# 51-2001-01-6_04_Power_Module_Schematic.net
KiCad netlist of a schematic drawn in Altium Designer
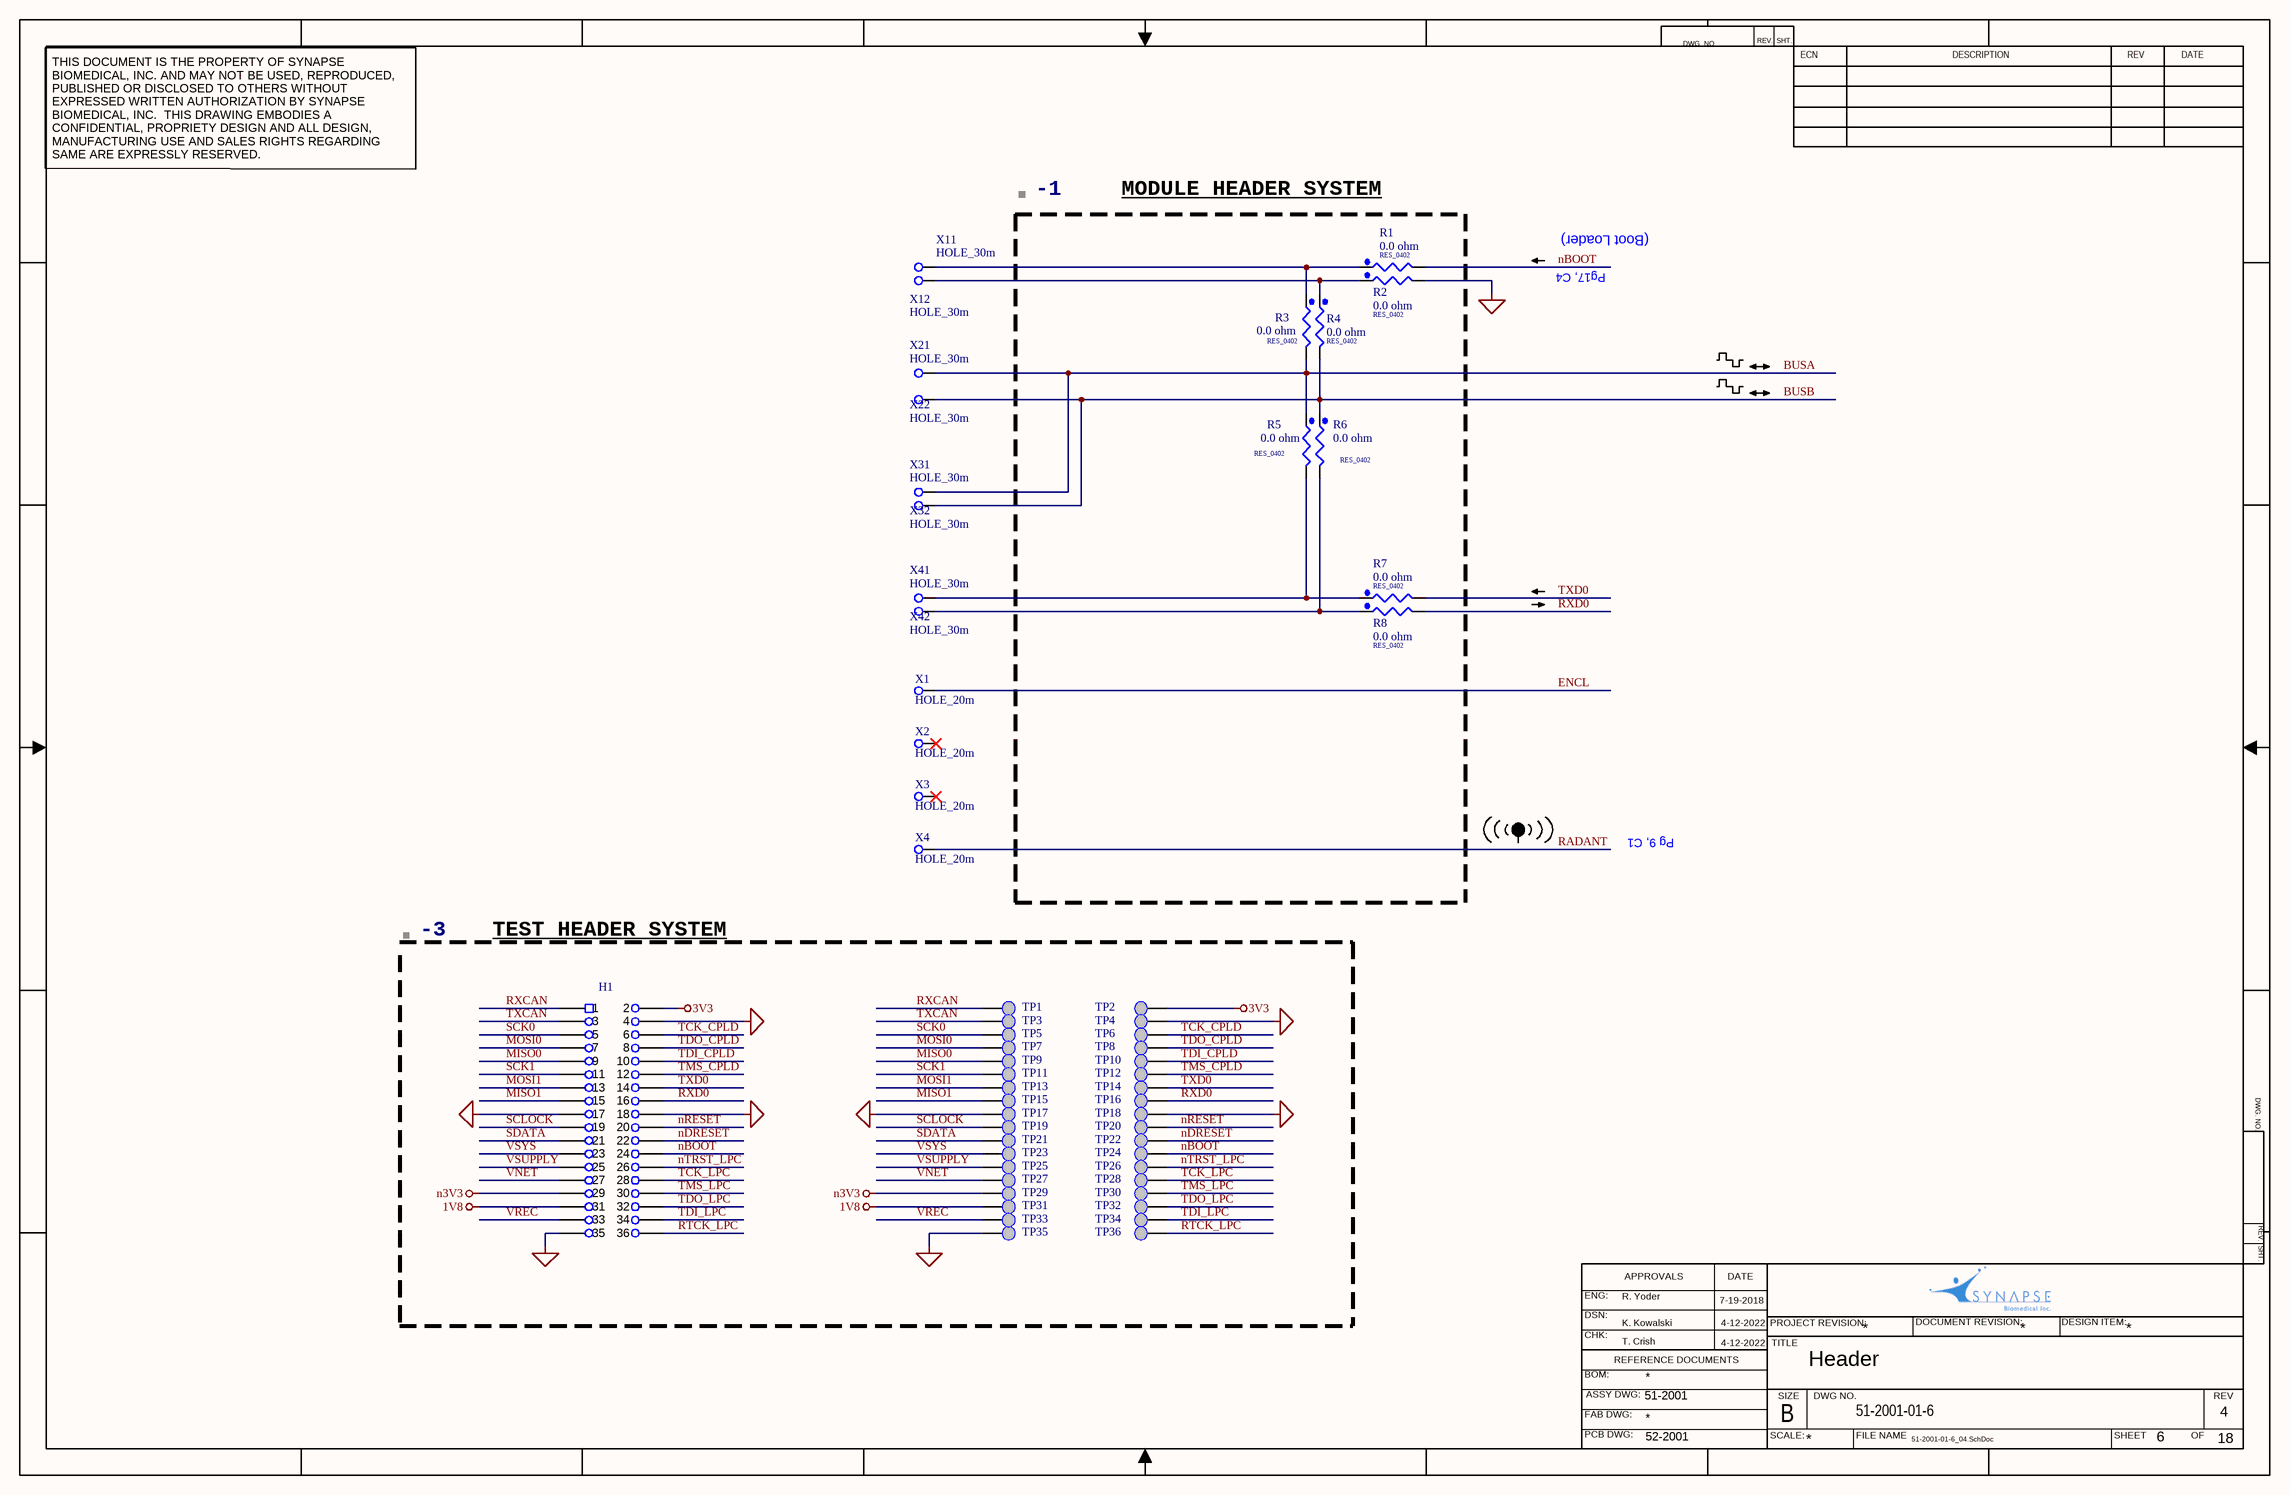
[diagram p0: 51-2001-01-6_04 Power Module Schematic.SchDoc]

(export (version "E")
  (design (tool "Eeschema 10.0.6"))
  (components
    (comp (ref "-1")
      (value "BOM_S1")
      (description "BOM item small graphic")
      (fields (field (name "XDESCRIPTION") "MODULE HEADER SYSTEM"))
      (libsource (lib "BOM_sym") (part "BOM_S1"))
    )
    (comp (ref "-3")
      (value "BOM_S1")
      (description "BOM item small graphic")
      (fields (field (name "XDESCRIPTION") "TEST HEADER SYSTEM"))
      (libsource (lib "BOM_sym") (part "BOM_S1"))
    )
    (comp (ref "H1")
      (value "0.1\"")
      (footprint "HEADER36")
      (description "0.1\" Header")
      (libsource (lib "NNPS Integrated Parts") (part "Header 2X18"))
    )
    (comp (ref "R1")
      (value "0.0 ohm")
      (footprint "RES_0402")
      (description "0.0 ohm, 1/16W, 0402, RoHS")
      (fields
        (field (name "MFR") "Vishay Dale")
        (field (name "PACKAGEDESCRIPTION") "RES_0402")
        (field (name "MPN") "CRCW04021K00FKED")
      )
      (libsource (lib "NNPS Integrated Parts") (part "MCR01MZPJ000"))
    )
    (comp (ref "R2")
      (value "0.0 ohm")
      (footprint "RES_0402")
      (description "0.0 ohm, 1/16W, 0402, RoHS")
      (fields
        (field (name "MFR") "Vishay Dale")
        (field (name "PACKAGEDESCRIPTION") "RES_0402")
        (field (name "MPN") "CRCW04021K00FKED")
      )
      (libsource (lib "NNPS Integrated Parts") (part "MCR01MZPJ000"))
    )
    (comp (ref "R3")
      (value "0.0 ohm")
      (footprint "RES_0402")
      (description "0.0 ohm, 1/16W, 0402, RoHS")
      (fields
        (field (name "MFR") "Vishay Dale")
        (field (name "PACKAGEDESCRIPTION") "RES_0402")
        (field (name "MPN") "CRCW04021K00FKED")
      )
      (libsource (lib "NNPS Integrated Parts") (part "MCR01MZPJ000"))
    )
    (comp (ref "R4")
      (value "0.0 ohm")
      (footprint "RES_0402")
      (description "0.0 ohm, 1/16W, 0402, RoHS")
      (fields
        (field (name "MFR") "Vishay Dale")
        (field (name "PACKAGEDESCRIPTION") "RES_0402")
        (field (name "MPN") "CRCW04021K00FKED")
      )
      (libsource (lib "NNPS Integrated Parts") (part "MCR01MZPJ000"))
    )
    (comp (ref "R5")
      (value "0.0 ohm")
      (footprint "RES_0402")
      (description "0.0 ohm, 1/16W, 0402, RoHS")
      (fields
        (field (name "MFR") "Vishay Dale")
        (field (name "PACKAGEDESCRIPTION") "RES_0402")
        (field (name "MPN") "CRCW04021K00FKED")
      )
      (libsource (lib "NNPS Integrated Parts") (part "MCR01MZPJ000"))
    )
    (comp (ref "R6")
      (value "0.0 ohm")
      (footprint "RES_0402")
      (description "0.0 ohm, 1/16W, 0402, RoHS")
      (fields
        (field (name "MFR") "Vishay Dale")
        (field (name "PACKAGEDESCRIPTION") "RES_0402")
        (field (name "MPN") "CRCW04021K00FKED")
      )
      (libsource (lib "NNPS Integrated Parts") (part "MCR01MZPJ000"))
    )
    (comp (ref "R7")
      (value "0.0 ohm")
      (footprint "RES_0402")
      (description "0.0 ohm, 1/16W, 0402, RoHS")
      (fields
        (field (name "MFR") "Vishay Dale")
        (field (name "PACKAGEDESCRIPTION") "RES_0402")
        (field (name "MPN") "CRCW04021K00FKED")
      )
      (libsource (lib "NNPS Integrated Parts") (part "MCR01MZPJ000"))
    )
    (comp (ref "R8")
      (value "0.0 ohm")
      (footprint "RES_0402")
      (description "0.0 ohm, 1/16W, 0402, RoHS")
      (fields
        (field (name "MFR") "Vishay Dale")
        (field (name "PACKAGEDESCRIPTION") "RES_0402")
        (field (name "MPN") "CRCW04021K00FKED")
      )
      (libsource (lib "NNPS Integrated Parts") (part "MCR01MZPJ000"))
    )
    (comp (ref "TP1")
      (value "Test Point")
      (footprint "TEST_POINT")
      (description "Test Point Pad 1.00 mm")
      (libsource (lib "PM1b") (part "TP"))
    )
    (comp (ref "TP2")
      (value "Test Point")
      (footprint "TEST_POINT")
      (description "Test Point Pad 1.00 mm")
      (libsource (lib "PM1b") (part "TP"))
    )
    (comp (ref "TP3")
      (value "Test Point")
      (footprint "TEST_POINT")
      (description "Test Point Pad 1.00 mm")
      (libsource (lib "PM1b") (part "TP"))
    )
    (comp (ref "TP4")
      (value "Test Point")
      (footprint "TEST_POINT")
      (description "Test Point Pad 1.00 mm")
      (libsource (lib "PM1b") (part "TP"))
    )
    (comp (ref "TP5")
      (value "Test Point")
      (footprint "TEST_POINT")
      (description "Test Point Pad 1.00 mm")
      (libsource (lib "PM1b") (part "TP"))
    )
    (comp (ref "TP6")
      (value "Test Point")
      (footprint "TEST_POINT")
      (description "Test Point Pad 1.00 mm")
      (libsource (lib "PM1b") (part "TP"))
    )
    (comp (ref "TP7")
      (value "Test Point")
      (footprint "TEST_POINT")
      (description "Test Point Pad 1.00 mm")
      (libsource (lib "PM1b") (part "TP"))
    )
    (comp (ref "TP8")
      (value "Test Point")
      (footprint "TEST_POINT")
      (description "Test Point Pad 1.00 mm")
      (libsource (lib "PM1b") (part "TP"))
    )
    (comp (ref "TP9")
      (value "Test Point")
      (footprint "TEST_POINT")
      (description "Test Point Pad 1.00 mm")
      (libsource (lib "PM1b") (part "TP"))
    )
    (comp (ref "TP10")
      (value "Test Point")
      (footprint "TEST_POINT")
      (description "Test Point Pad 1.00 mm")
      (libsource (lib "PM1b") (part "TP"))
    )
    (comp (ref "TP11")
      (value "Test Point")
      (footprint "TEST_POINT")
      (description "Test Point Pad 1.00 mm")
      (libsource (lib "PM1b") (part "TP"))
    )
    (comp (ref "TP12")
      (value "Test Point")
      (footprint "TEST_POINT")
      (description "Test Point Pad 1.00 mm")
      (libsource (lib "PM1b") (part "TP"))
    )
    (comp (ref "TP13")
      (value "Test Point")
      (footprint "TEST_POINT")
      (description "Test Point Pad 1.00 mm")
      (libsource (lib "PM1b") (part "TP"))
    )
    (comp (ref "TP14")
      (value "Test Point")
      (footprint "TEST_POINT")
      (description "Test Point Pad 1.00 mm")
      (libsource (lib "PM1b") (part "TP"))
    )
    (comp (ref "TP15")
      (value "Test Point")
      (footprint "TEST_POINT")
      (description "Test Point Pad 1.00 mm")
      (libsource (lib "PM1b") (part "TP"))
    )
    (comp (ref "TP16")
      (value "Test Point")
      (footprint "TEST_POINT")
      (description "Test Point Pad 1.00 mm")
      (libsource (lib "PM1b") (part "TP"))
    )
    (comp (ref "TP17")
      (value "Test Point")
      (footprint "TEST_POINT")
      (description "Test Point Pad 1.00 mm")
      (libsource (lib "PM1b") (part "TP"))
    )
    (comp (ref "TP18")
      (value "Test Point")
      (footprint "TEST_POINT")
      (description "Test Point Pad 1.00 mm")
      (libsource (lib "PM1b") (part "TP"))
    )
    (comp (ref "TP19")
      (value "Test Point")
      (footprint "TEST_POINT")
      (description "Test Point Pad 1.00 mm")
      (libsource (lib "PM1b") (part "TP"))
    )
    (comp (ref "TP20")
      (value "Test Point")
      (footprint "TEST_POINT")
      (description "Test Point Pad 1.00 mm")
      (libsource (lib "PM1b") (part "TP"))
    )
    (comp (ref "TP21")
      (value "Test Point")
      (footprint "TEST_POINT")
      (description "Test Point Pad 1.00 mm")
      (libsource (lib "PM1b") (part "TP"))
    )
    (comp (ref "TP22")
      (value "Test Point")
      (footprint "TEST_POINT")
      (description "Test Point Pad 1.00 mm")
      (libsource (lib "PM1b") (part "TP"))
    )
    (comp (ref "TP23")
      (value "Test Point")
      (footprint "TEST_POINT")
      (description "Test Point Pad 1.00 mm")
      (libsource (lib "PM1b") (part "TP"))
    )
    (comp (ref "TP24")
      (value "Test Point")
      (footprint "TEST_POINT")
      (description "Test Point Pad 1.00 mm")
      (libsource (lib "PM1b") (part "TP"))
    )
    (comp (ref "TP25")
      (value "Test Point")
      (footprint "TEST_POINT")
      (description "Test Point Pad 1.00 mm")
      (libsource (lib "PM1b") (part "TP"))
    )
    (comp (ref "TP26")
      (value "Test Point")
      (footprint "TEST_POINT")
      (description "Test Point Pad 1.00 mm")
      (libsource (lib "PM1b") (part "TP"))
    )
    (comp (ref "TP27")
      (value "Test Point")
      (footprint "TEST_POINT")
      (description "Test Point Pad 1.00 mm")
      (libsource (lib "PM1b") (part "TP"))
    )
    (comp (ref "TP28")
      (value "Test Point")
      (footprint "TEST_POINT")
      (description "Test Point Pad 1.00 mm")
      (libsource (lib "PM1b") (part "TP"))
    )
    (comp (ref "TP29")
      (value "Test Point")
      (footprint "TEST_POINT")
      (description "Test Point Pad 1.00 mm")
      (libsource (lib "PM1b") (part "TP"))
    )
    (comp (ref "TP30")
      (value "Test Point")
      (footprint "TEST_POINT")
      (description "Test Point Pad 1.00 mm")
      (libsource (lib "PM1b") (part "TP"))
    )
    (comp (ref "TP31")
      (value "Test Point")
      (footprint "TEST_POINT")
      (description "Test Point Pad 1.00 mm")
      (libsource (lib "PM1b") (part "TP"))
    )
    (comp (ref "TP32")
      (value "Test Point")
      (footprint "TEST_POINT")
      (description "Test Point Pad 1.00 mm")
      (libsource (lib "PM1b") (part "TP"))
    )
    (comp (ref "TP33")
      (value "Test Point")
      (footprint "TEST_POINT")
      (description "Test Point Pad 1.00 mm")
      (libsource (lib "PM1b") (part "TP"))
    )
    (comp (ref "TP34")
      (value "Test Point")
      (footprint "TEST_POINT")
      (description "Test Point Pad 1.00 mm")
      (libsource (lib "PM1b") (part "TP"))
    )
    (comp (ref "TP35")
      (value "Test Point")
      (footprint "TEST_POINT")
      (description "Test Point Pad 1.00 mm")
      (libsource (lib "PM1b") (part "TP"))
    )
    (comp (ref "TP36")
      (value "Test Point")
      (footprint "TEST_POINT")
      (description "Test Point Pad 1.00 mm")
      (libsource (lib "PM1b") (part "TP"))
    )
    (comp (ref "X1")
      (value "HOLE_20m")
      (footprint "FEEDHOLE_20mil")
      (description "Hole for 10mil diameter feedthrough")
      (libsource (lib "NNPS Integrated Parts") (part "HOLE_20m"))
    )
    (comp (ref "X2")
      (value "HOLE_20m")
      (footprint "FEEDHOLE_20mil")
      (description "Hole for 10mil diameter feedthrough")
      (libsource (lib "NNPS Integrated Parts") (part "HOLE_20m"))
    )
    (comp (ref "X3")
      (value "HOLE_20m")
      (footprint "FEEDHOLE_20mil")
      (description "Hole for 10mil diameter feedthrough")
      (libsource (lib "NNPS Integrated Parts") (part "HOLE_20m"))
    )
    (comp (ref "X4")
      (value "HOLE_20m")
      (footprint "FEEDHOLE_20mil")
      (description "Hole for 10mil diameter feedthrough")
      (libsource (lib "NNPS Integrated Parts") (part "HOLE_20m"))
    )
    (comp (ref "X11")
      (value "HOLE_30m")
      (footprint "FEEDHOLE_30mil")
      (description "Hole 30mil")
      (libsource (lib "NNPS Integrated Parts") (part "HOLE_30m"))
    )
    (comp (ref "X12")
      (value "HOLE_30m")
      (footprint "FEEDHOLE_30mil")
      (description "Hole 30mil")
      (libsource (lib "NNPS Integrated Parts") (part "HOLE_30m"))
    )
    (comp (ref "X21")
      (value "HOLE_30m")
      (footprint "FEEDHOLE_30mil")
      (description "Hole 30mil")
      (libsource (lib "NNPS Integrated Parts") (part "HOLE_30m"))
    )
    (comp (ref "X22")
      (value "HOLE_30m")
      (footprint "FEEDHOLE_30mil")
      (description "Hole 30mil")
      (libsource (lib "NNPS Integrated Parts") (part "HOLE_30m"))
    )
    (comp (ref "X31")
      (value "HOLE_30m")
      (footprint "FEEDHOLE_30mil")
      (description "Hole 30mil")
      (libsource (lib "NNPS Integrated Parts") (part "HOLE_30m"))
    )
    (comp (ref "X32")
      (value "HOLE_30m")
      (footprint "FEEDHOLE_30mil")
      (description "Hole 30mil")
      (libsource (lib "NNPS Integrated Parts") (part "HOLE_30m"))
    )
    (comp (ref "X41")
      (value "HOLE_30m")
      (footprint "FEEDHOLE_30mil")
      (description "Hole 30mil")
      (libsource (lib "NNPS Integrated Parts") (part "HOLE_30m"))
    )
    (comp (ref "X42")
      (value "HOLE_30m")
      (footprint "PCBComponent_11")
      (description "Hole 30mil")
      (libsource (lib "NNPS Integrated Parts") (part "HOLE_30m"))
    )
  )
  (nets
    (net (code "1") (name "/BUSA") (class "Default")
      (node (ref "R3") (pin "2") (pinfunction "2_2") (pintype "passive"))
      (node (ref "R5") (pin "1") (pinfunction "1_1") (pintype "passive"))
      (node (ref "X21") (pin "1") (pinfunction "1_1") (pintype "passive"))
      (node (ref "X31") (pin "1") (pinfunction "1_1") (pintype "passive"))
    )
    (net (code "2") (name "/BUSB") (class "Default")
      (node (ref "R4") (pin "2") (pinfunction "2_2") (pintype "passive"))
      (node (ref "R6") (pin "1") (pinfunction "1_1") (pintype "passive"))
      (node (ref "X22") (pin "1") (pinfunction "1_1") (pintype "passive"))
      (node (ref "X32") (pin "1") (pinfunction "1_1") (pintype "passive"))
    )
    (net (code "3") (name "/ENCL") (class "Default")
      (node (ref "X1") (pin "1") (pinfunction "1_1") (pintype "passive"))
    )
    (net (code "4") (name "/MISO0") (class "Default")
      (node (ref "H1") (pin "9") (pinfunction "9_9") (pintype "passive"))
      (node (ref "TP9") (pin "1") (pinfunction "TP_1") (pintype "passive"))
    )
    (net (code "5") (name "/MISO1") (class "Default")
      (node (ref "H1") (pin "15") (pinfunction "15_15") (pintype "passive"))
      (node (ref "TP15") (pin "1") (pinfunction "TP_1") (pintype "passive"))
    )
    (net (code "6") (name "/MOSI0") (class "Default")
      (node (ref "H1") (pin "7") (pinfunction "7_7") (pintype "passive"))
      (node (ref "TP7") (pin "1") (pinfunction "TP_1") (pintype "passive"))
    )
    (net (code "7") (name "/MOSI1") (class "Default")
      (node (ref "H1") (pin "13") (pinfunction "13_13") (pintype "passive"))
      (node (ref "TP13") (pin "1") (pinfunction "TP_1") (pintype "passive"))
    )
    (net (code "8") (name "/RADANT") (class "Default")
      (node (ref "X4") (pin "1") (pinfunction "1_1") (pintype "passive"))
    )
    (net (code "9") (name "/RTCK_LPC") (class "Default")
      (node (ref "H1") (pin "36") (pinfunction "36_36") (pintype "passive"))
      (node (ref "TP36") (pin "1") (pinfunction "TP_1") (pintype "passive"))
    )
    (net (code "10") (name "/RXCAN") (class "Default")
      (node (ref "H1") (pin "1") (pinfunction "1_1") (pintype "passive"))
      (node (ref "TP1") (pin "1") (pinfunction "TP_1") (pintype "passive"))
    )
    (net (code "11") (name "/RXD0") (class "Default")
      (node (ref "H1") (pin "16") (pinfunction "16_16") (pintype "passive"))
      (node (ref "R8") (pin "2") (pinfunction "2_2") (pintype "passive"))
      (node (ref "TP16") (pin "1") (pinfunction "TP_1") (pintype "passive"))
    )
    (net (code "12") (name "/SCK0") (class "Default")
      (node (ref "H1") (pin "5") (pinfunction "5_5") (pintype "passive"))
      (node (ref "TP5") (pin "1") (pinfunction "TP_1") (pintype "passive"))
    )
    (net (code "13") (name "/SCK1") (class "Default")
      (node (ref "H1") (pin "11") (pinfunction "11_11") (pintype "passive"))
      (node (ref "TP11") (pin "1") (pinfunction "TP_1") (pintype "passive"))
    )
    (net (code "14") (name "/SCLOCK") (class "Default")
      (node (ref "H1") (pin "19") (pinfunction "19_19") (pintype "passive"))
      (node (ref "TP19") (pin "1") (pinfunction "TP_1") (pintype "passive"))
    )
    (net (code "15") (name "/SDATA") (class "Default")
      (node (ref "H1") (pin "21") (pinfunction "21_21") (pintype "passive"))
      (node (ref "TP21") (pin "1") (pinfunction "TP_1") (pintype "passive"))
    )
    (net (code "16") (name "/TCK_CPLD") (class "Default")
      (node (ref "H1") (pin "6") (pinfunction "6_6") (pintype "passive"))
      (node (ref "TP6") (pin "1") (pinfunction "TP_1") (pintype "passive"))
    )
    (net (code "17") (name "/TCK_LPC") (class "Default")
      (node (ref "H1") (pin "28") (pinfunction "28_28") (pintype "passive"))
      (node (ref "TP28") (pin "1") (pinfunction "TP_1") (pintype "passive"))
    )
    (net (code "18") (name "/TDI_CPLD") (class "Default")
      (node (ref "H1") (pin "10") (pinfunction "10_10") (pintype "passive"))
      (node (ref "TP10") (pin "1") (pinfunction "TP_1") (pintype "passive"))
    )
    (net (code "19") (name "/TDI_LPC") (class "Default")
      (node (ref "H1") (pin "34") (pinfunction "34_34") (pintype "passive"))
      (node (ref "TP34") (pin "1") (pinfunction "TP_1") (pintype "passive"))
    )
    (net (code "20") (name "/TDO_CPLD") (class "Default")
      (node (ref "H1") (pin "8") (pinfunction "8_8") (pintype "passive"))
      (node (ref "TP8") (pin "1") (pinfunction "TP_1") (pintype "passive"))
    )
    (net (code "21") (name "/TDO_LPC") (class "Default")
      (node (ref "H1") (pin "32") (pinfunction "32_32") (pintype "passive"))
      (node (ref "TP32") (pin "1") (pinfunction "TP_1") (pintype "passive"))
    )
    (net (code "22") (name "/TMS_CPLD") (class "Default")
      (node (ref "H1") (pin "12") (pinfunction "12_12") (pintype "passive"))
      (node (ref "TP12") (pin "1") (pinfunction "TP_1") (pintype "passive"))
    )
    (net (code "23") (name "/TMS_LPC") (class "Default")
      (node (ref "H1") (pin "30") (pinfunction "30_30") (pintype "passive"))
      (node (ref "TP30") (pin "1") (pinfunction "TP_1") (pintype "passive"))
    )
    (net (code "24") (name "/TXCAN") (class "Default")
      (node (ref "H1") (pin "3") (pinfunction "3_3") (pintype "passive"))
      (node (ref "TP3") (pin "1") (pinfunction "TP_1") (pintype "passive"))
    )
    (net (code "25") (name "/TXD0") (class "Default")
      (node (ref "H1") (pin "14") (pinfunction "14_14") (pintype "passive"))
      (node (ref "R7") (pin "2") (pinfunction "2_2") (pintype "passive"))
      (node (ref "TP14") (pin "1") (pinfunction "TP_1") (pintype "passive"))
    )
    (net (code "26") (name "/VNET") (class "Default")
      (node (ref "H1") (pin "27") (pinfunction "27_27") (pintype "passive"))
      (node (ref "TP27") (pin "1") (pinfunction "TP_1") (pintype "passive"))
    )
    (net (code "27") (name "/VREC") (class "Default")
      (node (ref "H1") (pin "33") (pinfunction "33_33") (pintype "passive"))
      (node (ref "TP33") (pin "1") (pinfunction "TP_1") (pintype "passive"))
    )
    (net (code "28") (name "/VSUPPLY") (class "Default")
      (node (ref "H1") (pin "25") (pinfunction "25_25") (pintype "passive"))
      (node (ref "TP25") (pin "1") (pinfunction "TP_1") (pintype "passive"))
    )
    (net (code "29") (name "/VSYS") (class "Default")
      (node (ref "H1") (pin "23") (pinfunction "23_23") (pintype "passive"))
      (node (ref "TP23") (pin "1") (pinfunction "TP_1") (pintype "passive"))
    )
    (net (code "30") (name "/nBOOT") (class "Default")
      (node (ref "H1") (pin "24") (pinfunction "24_24") (pintype "passive"))
      (node (ref "R1") (pin "2") (pinfunction "2_2") (pintype "passive"))
      (node (ref "TP24") (pin "1") (pinfunction "TP_1") (pintype "passive"))
    )
    (net (code "31") (name "/nDRESET") (class "Default")
      (node (ref "H1") (pin "22") (pinfunction "22_22") (pintype "passive"))
      (node (ref "TP22") (pin "1") (pinfunction "TP_1") (pintype "passive"))
    )
    (net (code "32") (name "/nRESET") (class "Default")
      (node (ref "H1") (pin "20") (pinfunction "20_20") (pintype "passive"))
      (node (ref "TP20") (pin "1") (pinfunction "TP_1") (pintype "passive"))
    )
    (net (code "33") (name "/nTRST_LPC") (class "Default")
      (node (ref "H1") (pin "26") (pinfunction "26_26") (pintype "passive"))
      (node (ref "TP26") (pin "1") (pinfunction "TP_1") (pintype "passive"))
    )
    (net (code "34") (name "1V8") (class "Default")
      (node (ref "H1") (pin "31") (pinfunction "31_31") (pintype "passive"))
      (node (ref "TP31") (pin "1") (pinfunction "TP_1") (pintype "passive"))
    )
    (net (code "35") (name "3V3") (class "Default")
      (node (ref "H1") (pin "2") (pinfunction "2_2") (pintype "passive"))
      (node (ref "TP2") (pin "1") (pinfunction "TP_1") (pintype "passive"))
    )
    (net (code "36") (name "GND") (class "Default")
      (node (ref "H1") (pin "17") (pinfunction "17_17") (pintype "passive"))
      (node (ref "H1") (pin "18") (pinfunction "18_18") (pintype "passive"))
      (node (ref "H1") (pin "35") (pinfunction "35_35") (pintype "passive"))
      (node (ref "H1") (pin "4") (pinfunction "4_4") (pintype "passive"))
      (node (ref "R2") (pin "2") (pinfunction "2_2") (pintype "passive"))
      (node (ref "TP17") (pin "1") (pinfunction "TP_1") (pintype "passive"))
      (node (ref "TP18") (pin "1") (pinfunction "TP_1") (pintype "passive"))
      (node (ref "TP35") (pin "1") (pinfunction "TP_1") (pintype "passive"))
      (node (ref "TP4") (pin "1") (pinfunction "TP_1") (pintype "passive"))
    )
    (net (code "37") (name "Net-(R1-Pad1)") (class "Default")
      (node (ref "R1") (pin "1") (pinfunction "1_1") (pintype "passive"))
      (node (ref "R3") (pin "1") (pinfunction "1_1") (pintype "passive"))
      (node (ref "X11") (pin "1") (pinfunction "1_1") (pintype "passive"))
    )
    (net (code "38") (name "Net-(R2-Pad1)") (class "Default")
      (node (ref "R2") (pin "1") (pinfunction "1_1") (pintype "passive"))
      (node (ref "R4") (pin "1") (pinfunction "1_1") (pintype "passive"))
      (node (ref "X12") (pin "1") (pinfunction "1_1") (pintype "passive"))
    )
    (net (code "39") (name "Net-(R5-Pad2)") (class "Default")
      (node (ref "R5") (pin "2") (pinfunction "2_2") (pintype "passive"))
      (node (ref "R7") (pin "1") (pinfunction "1_1") (pintype "passive"))
      (node (ref "X41") (pin "1") (pinfunction "1_1") (pintype "passive"))
    )
    (net (code "40") (name "Net-(R6-Pad2)") (class "Default")
      (node (ref "R6") (pin "2") (pinfunction "2_2") (pintype "passive"))
      (node (ref "R8") (pin "1") (pinfunction "1_1") (pintype "passive"))
      (node (ref "X42") (pin "1") (pinfunction "1_1") (pintype "passive"))
    )
    (net (code "41") (name "n3V3") (class "Default")
      (node (ref "H1") (pin "29") (pinfunction "29_29") (pintype "passive"))
      (node (ref "TP29") (pin "1") (pinfunction "TP_1") (pintype "passive"))
    )
    (net (code "42") (name "unconnected-(X2-Pad1)") (class "Default")
      (node (ref "X2") (pin "1") (pinfunction "1_1") (pintype "passive+no_connect"))
    )
    (net (code "43") (name "unconnected-(X3-Pad1)") (class "Default")
      (node (ref "X3") (pin "1") (pinfunction "1_1") (pintype "passive+no_connect"))
    )
  )
)
